# vcf_lp_4p_24db-rev1.net
KiCad netlist of a schematic drawn in EAGLE
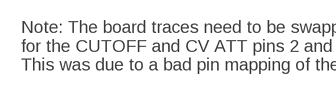
[diagram p0: schematic, sheet 1, part 1 of 2]
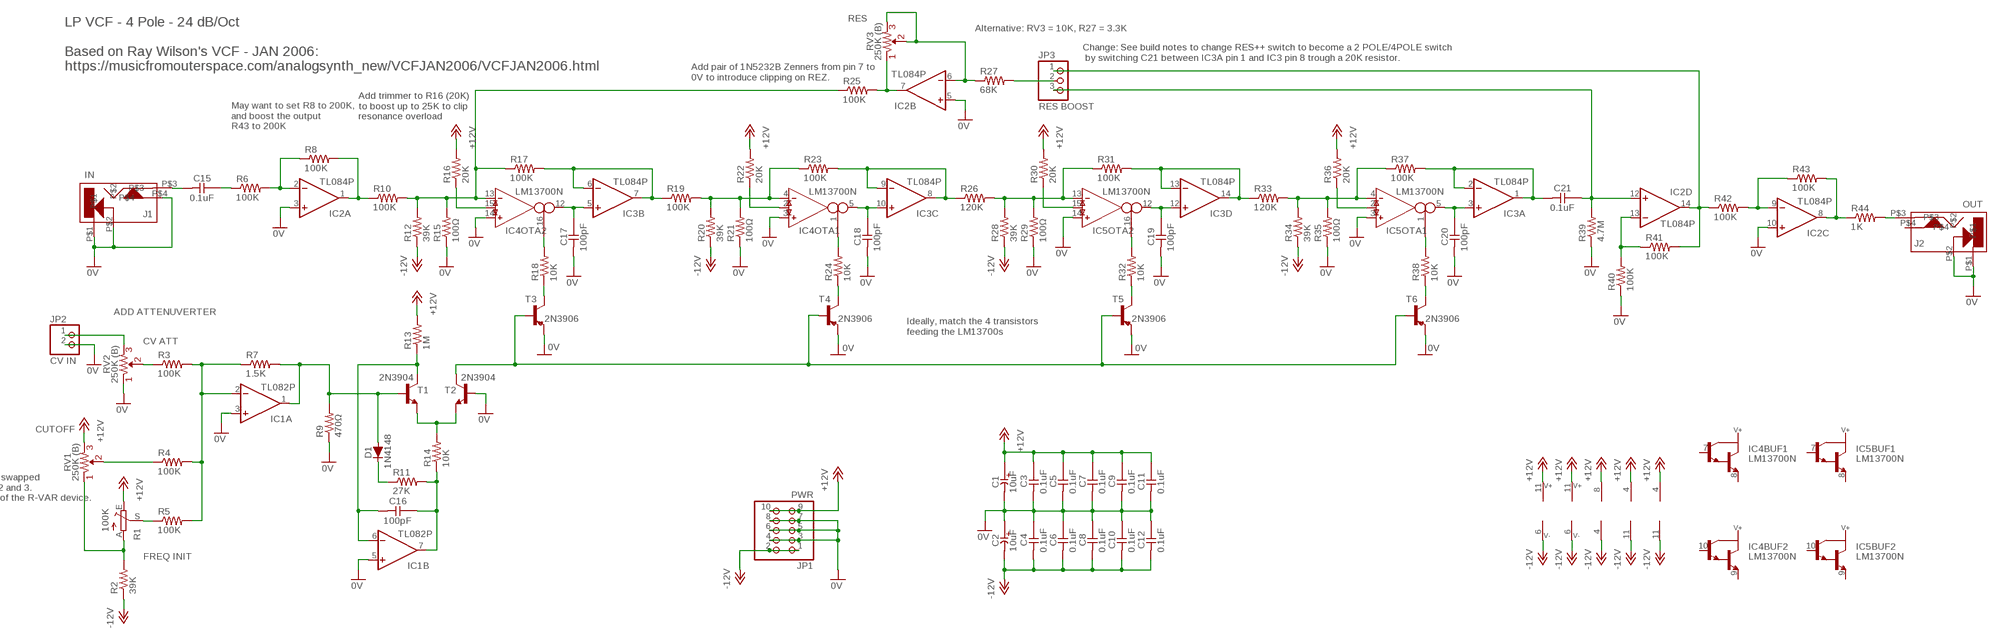
[diagram p1: schematic, sheet 1, part 2 of 2]

(export (version "E")
  (design (tool "Eeschema 10.0.6"))
  (components
    (comp (ref "C1")
      (value "10uF")
      (footprint "eagle-import:E2-5")
      (libsource (lib "eagle-import") (part "CE-USE2-5"))
    )
    (comp (ref "C2")
      (value "10uF")
      (footprint "eagle-import:E2-5")
      (libsource (lib "eagle-import") (part "CE-USE2-5"))
    )
    (comp (ref "C3")
      (value "0.1uF")
      (footprint "eagle-import:C025-024X044")
      (libsource (lib "eagle-import") (part "CC-US025-024X044"))
    )
    (comp (ref "C4")
      (value "0.1uF")
      (footprint "eagle-import:C025-024X044")
      (libsource (lib "eagle-import") (part "CC-US025-024X044"))
    )
    (comp (ref "C5")
      (value "0.1uF")
      (footprint "eagle-import:C025-024X044")
      (libsource (lib "eagle-import") (part "CC-US025-024X044"))
    )
    (comp (ref "C6")
      (value "0.1uF")
      (footprint "eagle-import:C025-024X044")
      (libsource (lib "eagle-import") (part "CC-US025-024X044"))
    )
    (comp (ref "C7")
      (value "0.1uF")
      (footprint "eagle-import:C025-024X044")
      (libsource (lib "eagle-import") (part "CC-US025-024X044"))
    )
    (comp (ref "C8")
      (value "0.1uF")
      (footprint "eagle-import:C025-024X044")
      (libsource (lib "eagle-import") (part "CC-US025-024X044"))
    )
    (comp (ref "C9")
      (value "0.1uF")
      (footprint "eagle-import:C025-024X044")
      (libsource (lib "eagle-import") (part "CC-US025-024X044"))
    )
    (comp (ref "C10")
      (value "0.1uF")
      (footprint "eagle-import:C025-024X044")
      (libsource (lib "eagle-import") (part "CC-US025-024X044"))
    )
    (comp (ref "C11")
      (value "0.1uF")
      (footprint "eagle-import:C025-024X044")
      (libsource (lib "eagle-import") (part "CC-US025-024X044"))
    )
    (comp (ref "C12")
      (value "0.1uF")
      (footprint "eagle-import:C025-024X044")
      (libsource (lib "eagle-import") (part "CC-US025-024X044"))
    )
    (comp (ref "C15")
      (value "0.1uF")
      (footprint "eagle-import:C025-024X044")
      (libsource (lib "eagle-import") (part "CC-US025-024X044"))
    )
    (comp (ref "C16")
      (value "100pF")
      (footprint "eagle-import:C025-024X044")
      (libsource (lib "eagle-import") (part "CC-US025-024X044"))
    )
    (comp (ref "C17")
      (value "100pF")
      (footprint "eagle-import:C025-024X044")
      (libsource (lib "eagle-import") (part "CC-US025-024X044"))
    )
    (comp (ref "C18")
      (value "100pF")
      (footprint "eagle-import:C025-024X044")
      (libsource (lib "eagle-import") (part "CC-US025-024X044"))
    )
    (comp (ref "C19")
      (value "100pF")
      (footprint "eagle-import:C025-024X044")
      (libsource (lib "eagle-import") (part "CC-US025-024X044"))
    )
    (comp (ref "C20")
      (value "100pF")
      (footprint "eagle-import:C025-024X044")
      (libsource (lib "eagle-import") (part "CC-US025-024X044"))
    )
    (comp (ref "C21")
      (value "0.1uF")
      (footprint "eagle-import:C025-024X044")
      (libsource (lib "eagle-import") (part "CC-US025-024X044"))
    )
    (comp (ref "D1")
      (value "1N4148")
      (footprint "eagle-import:DO35-7")
      (libsource (lib "eagle-import") (part "1N4148"))
    )
    (comp (ref "IC1")
      (value "TL082P")
      (footprint "eagle-import:DIL08")
      (libsource (lib "eagle-import") (part "TL082P"))
    )
    (comp (ref "IC2")
      (value "TL084P")
      (footprint "eagle-import:DIL14")
      (libsource (lib "eagle-import") (part "TL084P"))
    )
    (comp (ref "IC3")
      (value "TL084P")
      (footprint "eagle-import:DIL14")
      (libsource (lib "eagle-import") (part "TL084P"))
    )
    (comp (ref "IC4")
      (value "LM13700N")
      (footprint "eagle-import:DIL16")
      (libsource (lib "eagle-import") (part "LM13700N"))
    )
    (comp (ref "IC5")
      (value "LM13700N")
      (footprint "eagle-import:DIL16")
      (libsource (lib "eagle-import") (part "LM13700N"))
    )
    (comp (ref "J1")
      (value "IN")
      (footprint "eagle-import:CL1384")
      (libsource (lib "eagle-import") (part "CL1384"))
    )
    (comp (ref "J2")
      (value "OUT")
      (footprint "eagle-import:CL1384")
      (libsource (lib "eagle-import") (part "CL1384"))
    )
    (comp (ref "JP1")
      (value "PWR")
      (footprint "eagle-import:2X05")
      (libsource (lib "eagle-import") (part "PINHD-2X5"))
    )
    (comp (ref "JP2")
      (value "CV IN")
      (footprint "eagle-import:1X02")
      (libsource (lib "eagle-import") (part "PINHD-1X2"))
    )
    (comp (ref "JP3")
      (value "RES BOOST")
      (footprint "eagle-import:1X03")
      (libsource (lib "eagle-import") (part "PINHD-1X3"))
    )
    (comp (ref "R1")
      (value "100K")
      (footprint "eagle-import:CA6V")
      (libsource (lib "eagle-import") (part "TRIM_EU-CA6V"))
    )
    (comp (ref "R2")
      (value "39K")
      (footprint "eagle-import:0207_7")
      (libsource (lib "eagle-import") (part "R-US_0207/7"))
    )
    (comp (ref "R3")
      (value "100K")
      (footprint "eagle-import:0207_7")
      (libsource (lib "eagle-import") (part "R-US_0207/7"))
    )
    (comp (ref "R4")
      (value "100K")
      (footprint "eagle-import:0207_7")
      (libsource (lib "eagle-import") (part "R-US_0207/7"))
    )
    (comp (ref "R5")
      (value "100K")
      (footprint "eagle-import:0207_7")
      (libsource (lib "eagle-import") (part "R-US_0207/7"))
    )
    (comp (ref "R6")
      (value "100K")
      (footprint "eagle-import:0207_7")
      (libsource (lib "eagle-import") (part "R-US_0207/7"))
    )
    (comp (ref "R7")
      (value "1.5K")
      (footprint "eagle-import:0207_7")
      (libsource (lib "eagle-import") (part "R-US_0207/7"))
    )
    (comp (ref "R8")
      (value "100K")
      (footprint "eagle-import:0207_7")
      (libsource (lib "eagle-import") (part "R-US_0207/7"))
    )
    (comp (ref "R9")
      (value "470Ω")
      (footprint "eagle-import:0207_7")
      (libsource (lib "eagle-import") (part "R-US_0207/7"))
    )
    (comp (ref "R10")
      (value "100K")
      (footprint "eagle-import:0207_7")
      (libsource (lib "eagle-import") (part "R-US_0207/7"))
    )
    (comp (ref "R11")
      (value "27K")
      (footprint "eagle-import:0207_7")
      (libsource (lib "eagle-import") (part "R-US_0207/7"))
    )
    (comp (ref "R12")
      (value "39K")
      (footprint "eagle-import:0207_7")
      (libsource (lib "eagle-import") (part "R-US_0207/7"))
    )
    (comp (ref "R13")
      (value "1M")
      (footprint "eagle-import:0207_7")
      (libsource (lib "eagle-import") (part "R-US_0207/7"))
    )
    (comp (ref "R14")
      (value "10K")
      (footprint "eagle-import:0207_7")
      (libsource (lib "eagle-import") (part "R-US_0207/7"))
    )
    (comp (ref "R15")
      (value "100Ω")
      (footprint "eagle-import:0207_7")
      (libsource (lib "eagle-import") (part "R-US_0207/7"))
    )
    (comp (ref "R16")
      (value "20K")
      (footprint "eagle-import:0207_7")
      (libsource (lib "eagle-import") (part "R-US_0207/7"))
    )
    (comp (ref "R17")
      (value "100K")
      (footprint "eagle-import:0207_7")
      (libsource (lib "eagle-import") (part "R-US_0207/7"))
    )
    (comp (ref "R18")
      (value "10K")
      (footprint "eagle-import:0207_7")
      (libsource (lib "eagle-import") (part "R-US_0207/7"))
    )
    (comp (ref "R19")
      (value "100K")
      (footprint "eagle-import:0207_7")
      (libsource (lib "eagle-import") (part "R-US_0207/7"))
    )
    (comp (ref "R20")
      (value "39K")
      (footprint "eagle-import:0207_7")
      (libsource (lib "eagle-import") (part "R-US_0207/7"))
    )
    (comp (ref "R21")
      (value "100Ω")
      (footprint "eagle-import:0207_7")
      (libsource (lib "eagle-import") (part "R-US_0207/7"))
    )
    (comp (ref "R22")
      (value "20K")
      (footprint "eagle-import:0207_7")
      (libsource (lib "eagle-import") (part "R-US_0207/7"))
    )
    (comp (ref "R23")
      (value "100K")
      (footprint "eagle-import:0207_7")
      (libsource (lib "eagle-import") (part "R-US_0207/7"))
    )
    (comp (ref "R24")
      (value "10K")
      (footprint "eagle-import:0207_7")
      (libsource (lib "eagle-import") (part "R-US_0207/7"))
    )
    (comp (ref "R25")
      (value "100K")
      (footprint "eagle-import:0207_7")
      (libsource (lib "eagle-import") (part "R-US_0207/7"))
    )
    (comp (ref "R26")
      (value "120K")
      (footprint "eagle-import:0207_7")
      (libsource (lib "eagle-import") (part "R-US_0207/7"))
    )
    (comp (ref "R27")
      (value "68K")
      (footprint "eagle-import:0207_7")
      (libsource (lib "eagle-import") (part "R-US_0207/7"))
    )
    (comp (ref "R28")
      (value "39K")
      (footprint "eagle-import:0207_7")
      (libsource (lib "eagle-import") (part "R-US_0207/7"))
    )
    (comp (ref "R29")
      (value "100Ω")
      (footprint "eagle-import:0207_7")
      (libsource (lib "eagle-import") (part "R-US_0207/7"))
    )
    (comp (ref "R30")
      (value "20K")
      (footprint "eagle-import:0207_7")
      (libsource (lib "eagle-import") (part "R-US_0207/7"))
    )
    (comp (ref "R31")
      (value "100K")
      (footprint "eagle-import:0207_7")
      (libsource (lib "eagle-import") (part "R-US_0207/7"))
    )
    (comp (ref "R32")
      (value "10K")
      (footprint "eagle-import:0207_7")
      (libsource (lib "eagle-import") (part "R-US_0207/7"))
    )
    (comp (ref "R33")
      (value "120K")
      (footprint "eagle-import:0207_7")
      (libsource (lib "eagle-import") (part "R-US_0207/7"))
    )
    (comp (ref "R34")
      (value "39K")
      (footprint "eagle-import:0207_7")
      (libsource (lib "eagle-import") (part "R-US_0207/7"))
    )
    (comp (ref "R35")
      (value "100Ω")
      (footprint "eagle-import:0207_7")
      (libsource (lib "eagle-import") (part "R-US_0207/7"))
    )
    (comp (ref "R36")
      (value "20K")
      (footprint "eagle-import:0207_7")
      (libsource (lib "eagle-import") (part "R-US_0207/7"))
    )
    (comp (ref "R37")
      (value "100K")
      (footprint "eagle-import:0207_7")
      (libsource (lib "eagle-import") (part "R-US_0207/7"))
    )
    (comp (ref "R38")
      (value "10K")
      (footprint "eagle-import:0207_7")
      (libsource (lib "eagle-import") (part "R-US_0207/7"))
    )
    (comp (ref "R39")
      (value "4.7M")
      (footprint "eagle-import:0207_7")
      (libsource (lib "eagle-import") (part "R-US_0207/7"))
    )
    (comp (ref "R40")
      (value "100K")
      (footprint "eagle-import:0207_7")
      (libsource (lib "eagle-import") (part "R-US_0207/7"))
    )
    (comp (ref "R41")
      (value "100K")
      (footprint "eagle-import:0207_7")
      (libsource (lib "eagle-import") (part "R-US_0207/7"))
    )
    (comp (ref "R42")
      (value "100K")
      (footprint "eagle-import:0207_7")
      (libsource (lib "eagle-import") (part "R-US_0207/7"))
    )
    (comp (ref "R43")
      (value "100K")
      (footprint "eagle-import:0207_7")
      (libsource (lib "eagle-import") (part "R-US_0207/7"))
    )
    (comp (ref "R44")
      (value "1K")
      (footprint "eagle-import:0207_7")
      (libsource (lib "eagle-import") (part "R-US_0207/7"))
    )
    (comp (ref "RV1")
      (value "250K (B)")
      (footprint "eagle-import:_COMMON_3RP_1610N")
      (libsource (lib "eagle-import") (part "R-VARR-VAR-10"))
    )
    (comp (ref "RV2")
      (value "250K (B)")
      (footprint "eagle-import:_COMMON_3RP_1610N")
      (libsource (lib "eagle-import") (part "R-VARR-VAR-10"))
    )
    (comp (ref "RV3")
      (value "250K (B)")
      (footprint "eagle-import:_COMMON_3RP_1610N")
      (libsource (lib "eagle-import") (part "R-VARR-VAR-10"))
    )
    (comp (ref "T1")
      (value "2N3904")
      (footprint "eagle-import:TO92-EBC")
      (libsource (lib "eagle-import") (part "-NPN-TO92-EBC2N3904"))
    )
    (comp (ref "T2")
      (value "2N3904")
      (footprint "eagle-import:TO92-EBC")
      (libsource (lib "eagle-import") (part "-NPN-TO92-EBC2N3904"))
    )
    (comp (ref "T3")
      (value "2N3906")
      (footprint "eagle-import:TO92-EBC")
      (libsource (lib "eagle-import") (part "-PNP-TO92-EBC2N3906"))
    )
    (comp (ref "T4")
      (value "2N3906")
      (footprint "eagle-import:TO92-EBC")
      (libsource (lib "eagle-import") (part "-PNP-TO92-EBC2N3906"))
    )
    (comp (ref "T5")
      (value "2N3906")
      (footprint "eagle-import:TO92-EBC")
      (libsource (lib "eagle-import") (part "-PNP-TO92-EBC2N3906"))
    )
    (comp (ref "T6")
      (value "2N3906")
      (footprint "eagle-import:TO92-EBC")
      (libsource (lib "eagle-import") (part "-PNP-TO92-EBC2N3906"))
    )
  )
  (nets
    (net (code "1") (name "+12V") (class "Default")
      (node (ref "C1") (pin "+") (pinfunction "+_+") (pintype "passive"))
      (node (ref "C11") (pin "1") (pinfunction "1_1") (pintype "passive"))
      (node (ref "C3") (pin "1") (pinfunction "1_1") (pintype "passive"))
      (node (ref "C5") (pin "1") (pinfunction "1_1") (pintype "passive"))
      (node (ref "C7") (pin "1") (pinfunction "1_1") (pintype "passive"))
      (node (ref "C9") (pin "1") (pinfunction "1_1") (pintype "passive"))
      (node (ref "IC1") (pin "8") (pinfunction "V+_8") (pintype "power_in"))
      (node (ref "IC2") (pin "4") (pinfunction "V+_4") (pintype "power_in"))
      (node (ref "IC3") (pin "4") (pinfunction "V+_4") (pintype "power_in"))
      (node (ref "IC4") (pin "11") (pinfunction "V+_11") (pintype "power_in"))
      (node (ref "IC5") (pin "11") (pinfunction "V+_11") (pintype "power_in"))
      (node (ref "JP1") (pin "10") (pinfunction "10_10") (pintype "passive"))
      (node (ref "JP1") (pin "9") (pinfunction "9_9") (pintype "passive"))
      (node (ref "R1") (pin "E") (pinfunction "E_E") (pintype "passive"))
      (node (ref "R13") (pin "2") (pinfunction "2_2") (pintype "passive"))
      (node (ref "R16") (pin "2") (pinfunction "2_2") (pintype "passive"))
      (node (ref "R22") (pin "2") (pinfunction "2_2") (pintype "passive"))
      (node (ref "R30") (pin "2") (pinfunction "2_2") (pintype "passive"))
      (node (ref "R36") (pin "2") (pinfunction "2_2") (pintype "passive"))
      (node (ref "RV1") (pin "2") (pinfunction "2_2") (pintype "passive"))
    )
    (net (code "2") (name "-12V") (class "Default")
      (node (ref "C10") (pin "2") (pinfunction "2_2") (pintype "passive"))
      (node (ref "C12") (pin "2") (pinfunction "2_2") (pintype "passive"))
      (node (ref "C2") (pin "-") (pinfunction "-_-") (pintype "passive"))
      (node (ref "C4") (pin "2") (pinfunction "2_2") (pintype "passive"))
      (node (ref "C6") (pin "2") (pinfunction "2_2") (pintype "passive"))
      (node (ref "C8") (pin "2") (pinfunction "2_2") (pintype "passive"))
      (node (ref "IC1") (pin "4") (pinfunction "V-_4") (pintype "power_in"))
      (node (ref "IC2") (pin "11") (pinfunction "V-_11") (pintype "power_in"))
      (node (ref "IC3") (pin "11") (pinfunction "V-_11") (pintype "power_in"))
      (node (ref "IC4") (pin "6") (pinfunction "V-_6") (pintype "power_in"))
      (node (ref "IC5") (pin "6") (pinfunction "V-_6") (pintype "power_in"))
      (node (ref "JP1") (pin "1") (pinfunction "1_1") (pintype "passive"))
      (node (ref "JP1") (pin "2") (pinfunction "2_2") (pintype "passive"))
      (node (ref "R12") (pin "1") (pinfunction "1_1") (pintype "passive"))
      (node (ref "R2") (pin "1") (pinfunction "1_1") (pintype "passive"))
      (node (ref "R20") (pin "1") (pinfunction "1_1") (pintype "passive"))
      (node (ref "R28") (pin "1") (pinfunction "1_1") (pintype "passive"))
      (node (ref "R34") (pin "1") (pinfunction "1_1") (pintype "passive"))
    )
    (net (code "3") (name "0V") (class "Default")
      (node (ref "C1") (pin "-") (pinfunction "-_-") (pintype "passive"))
      (node (ref "C10") (pin "1") (pinfunction "1_1") (pintype "passive"))
      (node (ref "C11") (pin "2") (pinfunction "2_2") (pintype "passive"))
      (node (ref "C12") (pin "1") (pinfunction "1_1") (pintype "passive"))
      (node (ref "C17") (pin "2") (pinfunction "2_2") (pintype "passive"))
      (node (ref "C18") (pin "2") (pinfunction "2_2") (pintype "passive"))
      (node (ref "C19") (pin "2") (pinfunction "2_2") (pintype "passive"))
      (node (ref "C2") (pin "+") (pinfunction "+_+") (pintype "passive"))
      (node (ref "C20") (pin "2") (pinfunction "2_2") (pintype "passive"))
      (node (ref "C3") (pin "2") (pinfunction "2_2") (pintype "passive"))
      (node (ref "C4") (pin "1") (pinfunction "1_1") (pintype "passive"))
      (node (ref "C5") (pin "2") (pinfunction "2_2") (pintype "passive"))
      (node (ref "C6") (pin "1") (pinfunction "1_1") (pintype "passive"))
      (node (ref "C7") (pin "2") (pinfunction "2_2") (pintype "passive"))
      (node (ref "C8") (pin "1") (pinfunction "1_1") (pintype "passive"))
      (node (ref "C9") (pin "2") (pinfunction "2_2") (pintype "passive"))
      (node (ref "IC1") (pin "3") (pinfunction "+IN_3") (pintype "input"))
      (node (ref "IC1") (pin "5") (pinfunction "+IN_5") (pintype "input"))
      (node (ref "IC2") (pin "10") (pinfunction "+IN_10") (pintype "input"))
      (node (ref "IC2") (pin "3") (pinfunction "+IN_3") (pintype "input"))
      (node (ref "IC2") (pin "5") (pinfunction "+IN_5") (pintype "input"))
      (node (ref "IC4") (pin "14") (pinfunction "IN_P_14") (pintype "input"))
      (node (ref "IC4") (pin "3") (pinfunction "IN_P_3") (pintype "input"))
      (node (ref "IC5") (pin "14") (pinfunction "IN_P_14") (pintype "input"))
      (node (ref "IC5") (pin "3") (pinfunction "IN_P_3") (pintype "input"))
      (node (ref "J1") (pin "P$1") (pinfunction "P$1_P$1") (pintype "bidirectional"))
      (node (ref "J1") (pin "P$2") (pinfunction "P$2_P$2") (pintype "bidirectional"))
      (node (ref "J1") (pin "P$4") (pinfunction "P$4_P$4") (pintype "bidirectional"))
      (node (ref "J2") (pin "P$1") (pinfunction "P$1_P$1") (pintype "bidirectional"))
      (node (ref "J2") (pin "P$2") (pinfunction "P$2_P$2") (pintype "bidirectional"))
      (node (ref "JP1") (pin "3") (pinfunction "3_3") (pintype "passive"))
      (node (ref "JP1") (pin "4") (pinfunction "4_4") (pintype "passive"))
      (node (ref "JP1") (pin "5") (pinfunction "5_5") (pintype "passive"))
      (node (ref "JP1") (pin "6") (pinfunction "6_6") (pintype "passive"))
      (node (ref "JP1") (pin "7") (pinfunction "7_7") (pintype "passive"))
      (node (ref "JP1") (pin "8") (pinfunction "8_8") (pintype "passive"))
      (node (ref "JP2") (pin "2") (pinfunction "2_2") (pintype "passive"))
      (node (ref "R15") (pin "1") (pinfunction "1_1") (pintype "passive"))
      (node (ref "R21") (pin "1") (pinfunction "1_1") (pintype "passive"))
      (node (ref "R29") (pin "1") (pinfunction "1_1") (pintype "passive"))
      (node (ref "R35") (pin "1") (pinfunction "1_1") (pintype "passive"))
      (node (ref "R39") (pin "1") (pinfunction "1_1") (pintype "passive"))
      (node (ref "R40") (pin "1") (pinfunction "1_1") (pintype "passive"))
      (node (ref "R9") (pin "1") (pinfunction "1_1") (pintype "passive"))
      (node (ref "RV2") (pin "1") (pinfunction "1_1") (pintype "passive"))
      (node (ref "T2") (pin "B") (pinfunction "B_B") (pintype "passive"))
      (node (ref "T3") (pin "E") (pinfunction "E_E") (pintype "passive"))
      (node (ref "T4") (pin "E") (pinfunction "E_E") (pintype "passive"))
      (node (ref "T5") (pin "E") (pinfunction "E_E") (pintype "passive"))
      (node (ref "T6") (pin "E") (pinfunction "E_E") (pintype "passive"))
    )
    (net (code "4") (name "Net-(C15-Pad1)") (class "Default")
      (node (ref "C15") (pin "1") (pinfunction "1_1") (pintype "passive"))
      (node (ref "R6") (pin "1") (pinfunction "1_1") (pintype "passive"))
    )
    (net (code "5") (name "Net-(C15-Pad2)") (class "Default")
      (node (ref "C15") (pin "2") (pinfunction "2_2") (pintype "passive"))
      (node (ref "J1") (pin "P$3") (pinfunction "P$3_P$3") (pintype "bidirectional"))
    )
    (net (code "6") (name "Net-(D1-PadC)") (class "Default")
      (node (ref "D1") (pin "C") (pinfunction "C_C") (pintype "passive"))
      (node (ref "R11") (pin "1") (pinfunction "1_1") (pintype "passive"))
    )
    (net (code "7") (name "Net-(IC1A--IN)") (class "Default")
      (node (ref "IC1") (pin "2") (pinfunction "-IN_2") (pintype "input"))
      (node (ref "R3") (pin "2") (pinfunction "2_2") (pintype "passive"))
      (node (ref "R4") (pin "2") (pinfunction "2_2") (pintype "passive"))
      (node (ref "R5") (pin "2") (pinfunction "2_2") (pintype "passive"))
      (node (ref "R7") (pin "1") (pinfunction "1_1") (pintype "passive"))
    )
    (net (code "8") (name "Net-(IC1A-OUT)") (class "Default")
      (node (ref "D1") (pin "A") (pinfunction "A_A") (pintype "passive"))
      (node (ref "IC1") (pin "1") (pinfunction "OUT_1") (pintype "output"))
      (node (ref "R7") (pin "2") (pinfunction "2_2") (pintype "passive"))
      (node (ref "R9") (pin "2") (pinfunction "2_2") (pintype "passive"))
      (node (ref "T1") (pin "B") (pinfunction "B_B") (pintype "passive"))
    )
    (net (code "9") (name "Net-(IC1B--IN)") (class "Default")
      (node (ref "C16") (pin "2") (pinfunction "2_2") (pintype "passive"))
      (node (ref "IC1") (pin "6") (pinfunction "-IN_6") (pintype "input"))
      (node (ref "R13") (pin "1") (pinfunction "1_1") (pintype "passive"))
      (node (ref "T1") (pin "C") (pinfunction "C_C") (pintype "passive"))
    )
    (net (code "10") (name "Net-(IC1B-OUT)") (class "Default")
      (node (ref "C16") (pin "1") (pinfunction "1_1") (pintype "passive"))
      (node (ref "IC1") (pin "7") (pinfunction "OUT_7") (pintype "output"))
      (node (ref "R11") (pin "2") (pinfunction "2_2") (pintype "passive"))
      (node (ref "R14") (pin "1") (pinfunction "1_1") (pintype "passive"))
    )
    (net (code "11") (name "Net-(IC2A--IN)") (class "Default")
      (node (ref "IC2") (pin "2") (pinfunction "-IN_2") (pintype "input"))
      (node (ref "R6") (pin "2") (pinfunction "2_2") (pintype "passive"))
      (node (ref "R8") (pin "1") (pinfunction "1_1") (pintype "passive"))
    )
    (net (code "12") (name "Net-(IC2A-OUT)") (class "Default")
      (node (ref "IC2") (pin "1") (pinfunction "OUT_1") (pintype "output"))
      (node (ref "R10") (pin "1") (pinfunction "1_1") (pintype "passive"))
      (node (ref "R8") (pin "2") (pinfunction "2_2") (pintype "passive"))
    )
    (net (code "13") (name "Net-(IC2B--IN)") (class "Default")
      (node (ref "IC2") (pin "6") (pinfunction "-IN_6") (pintype "input"))
      (node (ref "R27") (pin "1") (pinfunction "1_1") (pintype "passive"))
      (node (ref "RV3") (pin "2") (pinfunction "2_2") (pintype "passive"))
      (node (ref "RV3") (pin "3") (pinfunction "P$1_3") (pintype "passive"))
    )
    (net (code "14") (name "Net-(IC2B-OUT)") (class "Default")
      (node (ref "IC2") (pin "7") (pinfunction "OUT_7") (pintype "output"))
      (node (ref "R25") (pin "2") (pinfunction "2_2") (pintype "passive"))
      (node (ref "RV3") (pin "1") (pinfunction "1_1") (pintype "passive"))
    )
    (net (code "15") (name "Net-(IC2C--IN)") (class "Default")
      (node (ref "IC2") (pin "9") (pinfunction "-IN_9") (pintype "input"))
      (node (ref "R42") (pin "2") (pinfunction "2_2") (pintype "passive"))
      (node (ref "R43") (pin "1") (pinfunction "1_1") (pintype "passive"))
    )
    (net (code "16") (name "Net-(IC2C-OUT)") (class "Default")
      (node (ref "IC2") (pin "8") (pinfunction "OUT_8") (pintype "output"))
      (node (ref "R43") (pin "2") (pinfunction "2_2") (pintype "passive"))
      (node (ref "R44") (pin "1") (pinfunction "1_1") (pintype "passive"))
    )
    (net (code "17") (name "Net-(IC2D-+IN)") (class "Default")
      (node (ref "C21") (pin "1") (pinfunction "1_1") (pintype "passive"))
      (node (ref "IC2") (pin "12") (pinfunction "+IN_12") (pintype "input"))
      (node (ref "JP3") (pin "3") (pinfunction "3_3") (pintype "passive"))
      (node (ref "R39") (pin "2") (pinfunction "2_2") (pintype "passive"))
    )
    (net (code "18") (name "Net-(IC2D--IN)") (class "Default")
      (node (ref "IC2") (pin "13") (pinfunction "-IN_13") (pintype "input"))
      (node (ref "R40") (pin "2") (pinfunction "2_2") (pintype "passive"))
      (node (ref "R41") (pin "1") (pinfunction "1_1") (pintype "passive"))
    )
    (net (code "19") (name "Net-(IC2D-OUT)") (class "Default")
      (node (ref "IC2") (pin "14") (pinfunction "OUT_14") (pintype "output"))
      (node (ref "JP3") (pin "1") (pinfunction "1_1") (pintype "passive"))
      (node (ref "R41") (pin "2") (pinfunction "2_2") (pintype "passive"))
      (node (ref "R42") (pin "1") (pinfunction "1_1") (pintype "passive"))
    )
    (net (code "20") (name "Net-(IC3A-+IN)") (class "Default")
      (node (ref "C20") (pin "1") (pinfunction "1_1") (pintype "passive"))
      (node (ref "IC3") (pin "3") (pinfunction "+IN_3") (pintype "input"))
      (node (ref "IC5") (pin "5") (pinfunction "OUT_5") (pintype "output"))
    )
    (net (code "21") (name "Net-(IC3A--IN)") (class "Default")
      (node (ref "C21") (pin "2") (pinfunction "2_2") (pintype "passive"))
      (node (ref "IC3") (pin "1") (pinfunction "OUT_1") (pintype "output"))
      (node (ref "IC3") (pin "2") (pinfunction "-IN_2") (pintype "input"))
      (node (ref "R37") (pin "2") (pinfunction "2_2") (pintype "passive"))
    )
    (net (code "22") (name "Net-(IC3B-+IN)") (class "Default")
      (node (ref "C17") (pin "1") (pinfunction "1_1") (pintype "passive"))
      (node (ref "IC3") (pin "5") (pinfunction "+IN_5") (pintype "input"))
      (node (ref "IC4") (pin "12") (pinfunction "OUT_12") (pintype "output"))
    )
    (net (code "23") (name "Net-(IC3B--IN)") (class "Default")
      (node (ref "IC3") (pin "6") (pinfunction "-IN_6") (pintype "input"))
      (node (ref "IC3") (pin "7") (pinfunction "OUT_7") (pintype "output"))
      (node (ref "R17") (pin "2") (pinfunction "2_2") (pintype "passive"))
      (node (ref "R19") (pin "1") (pinfunction "1_1") (pintype "passive"))
    )
    (net (code "24") (name "Net-(IC3C-+IN)") (class "Default")
      (node (ref "C18") (pin "1") (pinfunction "1_1") (pintype "passive"))
      (node (ref "IC3") (pin "10") (pinfunction "+IN_10") (pintype "input"))
      (node (ref "IC4") (pin "5") (pinfunction "OUT_5") (pintype "output"))
    )
    (net (code "25") (name "Net-(IC3C--IN)") (class "Default")
      (node (ref "IC3") (pin "8") (pinfunction "OUT_8") (pintype "output"))
      (node (ref "IC3") (pin "9") (pinfunction "-IN_9") (pintype "input"))
      (node (ref "R23") (pin "2") (pinfunction "2_2") (pintype "passive"))
      (node (ref "R26") (pin "1") (pinfunction "1_1") (pintype "passive"))
    )
    (net (code "26") (name "Net-(IC3D-+IN)") (class "Default")
      (node (ref "C19") (pin "1") (pinfunction "1_1") (pintype "passive"))
      (node (ref "IC3") (pin "12") (pinfunction "+IN_12") (pintype "input"))
      (node (ref "IC5") (pin "12") (pinfunction "OUT_12") (pintype "output"))
    )
    (net (code "27") (name "Net-(IC3D--IN)") (class "Default")
      (node (ref "IC3") (pin "13") (pinfunction "-IN_13") (pintype "input"))
      (node (ref "IC3") (pin "14") (pinfunction "OUT_14") (pintype "output"))
      (node (ref "R31") (pin "2") (pinfunction "2_2") (pintype "passive"))
      (node (ref "R33") (pin "1") (pinfunction "1_1") (pintype "passive"))
    )
    (net (code "28") (name "Net-(IC4C-IN_N)") (class "Default")
      (node (ref "IC4") (pin "4") (pinfunction "IN_N_4") (pintype "input"))
      (node (ref "R19") (pin "2") (pinfunction "2_2") (pintype "passive"))
      (node (ref "R20") (pin "2") (pinfunction "2_2") (pintype "passive"))
      (node (ref "R21") (pin "2") (pinfunction "2_2") (pintype "passive"))
      (node (ref "R23") (pin "1") (pinfunction "1_1") (pintype "passive"))
    )
    (net (code "29") (name "Net-(IC4C-I_BIAS)") (class "Default")
      (node (ref "IC4") (pin "1") (pinfunction "I_BIAS_1") (pintype "input"))
      (node (ref "R24") (pin "2") (pinfunction "2_2") (pintype "passive"))
    )
    (net (code "30") (name "Net-(IC4C-I_DIODE)") (class "Default")
      (node (ref "IC4") (pin "2") (pinfunction "I_DIODE_2") (pintype "input"))
      (node (ref "R22") (pin "1") (pinfunction "1_1") (pintype "passive"))
    )
    (net (code "31") (name "Net-(IC4D-IN_N)") (class "Default")
      (node (ref "IC4") (pin "13") (pinfunction "IN_N_13") (pintype "input"))
      (node (ref "R10") (pin "2") (pinfunction "2_2") (pintype "passive"))
      (node (ref "R12") (pin "2") (pinfunction "2_2") (pintype "passive"))
      (node (ref "R15") (pin "2") (pinfunction "2_2") (pintype "passive"))
      (node (ref "R17") (pin "1") (pinfunction "1_1") (pintype "passive"))
      (node (ref "R25") (pin "1") (pinfunction "1_1") (pintype "passive"))
    )
    (net (code "32") (name "Net-(IC4D-I_BIAS)") (class "Default")
      (node (ref "IC4") (pin "16") (pinfunction "I_BIAS_16") (pintype "input"))
      (node (ref "R18") (pin "2") (pinfunction "2_2") (pintype "passive"))
    )
    (net (code "33") (name "Net-(IC4D-I_DIODE)") (class "Default")
      (node (ref "IC4") (pin "15") (pinfunction "I_DIODE_15") (pintype "input"))
      (node (ref "R16") (pin "1") (pinfunction "1_1") (pintype "passive"))
    )
    (net (code "34") (name "Net-(IC5C-IN_N)") (class "Default")
      (node (ref "IC5") (pin "4") (pinfunction "IN_N_4") (pintype "input"))
      (node (ref "R33") (pin "2") (pinfunction "2_2") (pintype "passive"))
      (node (ref "R34") (pin "2") (pinfunction "2_2") (pintype "passive"))
      (node (ref "R35") (pin "2") (pinfunction "2_2") (pintype "passive"))
      (node (ref "R37") (pin "1") (pinfunction "1_1") (pintype "passive"))
    )
    (net (code "35") (name "Net-(IC5C-I_BIAS)") (class "Default")
      (node (ref "IC5") (pin "1") (pinfunction "I_BIAS_1") (pintype "input"))
      (node (ref "R38") (pin "2") (pinfunction "2_2") (pintype "passive"))
    )
    (net (code "36") (name "Net-(IC5C-I_DIODE)") (class "Default")
      (node (ref "IC5") (pin "2") (pinfunction "I_DIODE_2") (pintype "input"))
      (node (ref "R36") (pin "1") (pinfunction "1_1") (pintype "passive"))
    )
    (net (code "37") (name "Net-(IC5D-IN_N)") (class "Default")
      (node (ref "IC5") (pin "13") (pinfunction "IN_N_13") (pintype "input"))
      (node (ref "R26") (pin "2") (pinfunction "2_2") (pintype "passive"))
      (node (ref "R28") (pin "2") (pinfunction "2_2") (pintype "passive"))
      (node (ref "R29") (pin "2") (pinfunction "2_2") (pintype "passive"))
      (node (ref "R31") (pin "1") (pinfunction "1_1") (pintype "passive"))
    )
    (net (code "38") (name "Net-(IC5D-I_BIAS)") (class "Default")
      (node (ref "IC5") (pin "16") (pinfunction "I_BIAS_16") (pintype "input"))
      (node (ref "R32") (pin "2") (pinfunction "2_2") (pintype "passive"))
    )
    (net (code "39") (name "Net-(IC5D-I_DIODE)") (class "Default")
      (node (ref "IC5") (pin "15") (pinfunction "I_DIODE_15") (pintype "input"))
      (node (ref "R30") (pin "1") (pinfunction "1_1") (pintype "passive"))
    )
    (net (code "40") (name "Net-(J2-PadP$3)") (class "Default")
      (node (ref "J2") (pin "P$3") (pinfunction "P$3_P$3") (pintype "bidirectional"))
      (node (ref "R44") (pin "2") (pinfunction "2_2") (pintype "passive"))
    )
    (net (code "41") (name "Net-(JP2-Pad1)") (class "Default")
      (node (ref "JP2") (pin "1") (pinfunction "1_1") (pintype "passive"))
      (node (ref "RV2") (pin "2") (pinfunction "2_2") (pintype "passive"))
    )
    (net (code "42") (name "Net-(JP3-Pad2)") (class "Default")
      (node (ref "JP3") (pin "2") (pinfunction "2_2") (pintype "passive"))
      (node (ref "R27") (pin "2") (pinfunction "2_2") (pintype "passive"))
    )
    (net (code "43") (name "Net-(R1-PadA)") (class "Default")
      (node (ref "R1") (pin "A") (pinfunction "A_A") (pintype "passive"))
      (node (ref "R2") (pin "2") (pinfunction "2_2") (pintype "passive"))
      (node (ref "RV1") (pin "1") (pinfunction "1_1") (pintype "passive"))
    )
    (net (code "44") (name "Net-(R1-PadS)") (class "Default")
      (node (ref "R1") (pin "S") (pinfunction "S_S") (pintype "passive"))
      (node (ref "R5") (pin "1") (pinfunction "1_1") (pintype "passive"))
    )
    (net (code "45") (name "Net-(R14-Pad2)") (class "Default")
      (node (ref "R14") (pin "2") (pinfunction "2_2") (pintype "passive"))
      (node (ref "T1") (pin "E") (pinfunction "E_E") (pintype "passive"))
      (node (ref "T2") (pin "E") (pinfunction "E_E") (pintype "passive"))
    )
    (net (code "46") (name "Net-(R18-Pad1)") (class "Default")
      (node (ref "R18") (pin "1") (pinfunction "1_1") (pintype "passive"))
      (node (ref "T3") (pin "C") (pinfunction "C_C") (pintype "passive"))
    )
    (net (code "47") (name "Net-(R24-Pad1)") (class "Default")
      (node (ref "R24") (pin "1") (pinfunction "1_1") (pintype "passive"))
      (node (ref "T4") (pin "C") (pinfunction "C_C") (pintype "passive"))
    )
    (net (code "48") (name "Net-(R32-Pad1)") (class "Default")
      (node (ref "R32") (pin "1") (pinfunction "1_1") (pintype "passive"))
      (node (ref "T5") (pin "C") (pinfunction "C_C") (pintype "passive"))
    )
    (net (code "49") (name "Net-(R38-Pad1)") (class "Default")
      (node (ref "R38") (pin "1") (pinfunction "1_1") (pintype "passive"))
      (node (ref "T6") (pin "C") (pinfunction "C_C") (pintype "passive"))
    )
    (net (code "50") (name "Net-(RV1-P$1)") (class "Default")
      (node (ref "R4") (pin "1") (pinfunction "1_1") (pintype "passive"))
      (node (ref "RV1") (pin "3") (pinfunction "P$1_3") (pintype "passive"))
    )
    (net (code "51") (name "Net-(RV2-P$1)") (class "Default")
      (node (ref "R3") (pin "1") (pinfunction "1_1") (pintype "passive"))
      (node (ref "RV2") (pin "3") (pinfunction "P$1_3") (pintype "passive"))
    )
    (net (code "52") (name "Net-(T2-PadC)") (class "Default")
      (node (ref "T2") (pin "C") (pinfunction "C_C") (pintype "passive"))
      (node (ref "T3") (pin "B") (pinfunction "B_B") (pintype "passive"))
      (node (ref "T4") (pin "B") (pinfunction "B_B") (pintype "passive"))
      (node (ref "T5") (pin "B") (pinfunction "B_B") (pintype "passive"))
      (node (ref "T6") (pin "B") (pinfunction "B_B") (pintype "passive"))
    )
    (net (code "53") (name "unconnected-(IC4A-B-Pad7)") (class "Default")
      (node (ref "IC4") (pin "7") (pinfunction "B_7") (pintype "passive"))
    )
    (net (code "54") (name "unconnected-(IC4A-E-Pad8)") (class "Default")
      (node (ref "IC4") (pin "8") (pinfunction "E_8") (pintype "passive"))
    )
    (net (code "55") (name "unconnected-(IC4B-B-Pad10)") (class "Default")
      (node (ref "IC4") (pin "10") (pinfunction "B_10") (pintype "passive"))
    )
    (net (code "56") (name "unconnected-(IC4B-E-Pad9)") (class "Default")
      (node (ref "IC4") (pin "9") (pinfunction "E_9") (pintype "passive"))
    )
    (net (code "57") (name "unconnected-(IC5A-B-Pad7)") (class "Default")
      (node (ref "IC5") (pin "7") (pinfunction "B_7") (pintype "passive"))
    )
    (net (code "58") (name "unconnected-(IC5A-E-Pad8)") (class "Default")
      (node (ref "IC5") (pin "8") (pinfunction "E_8") (pintype "passive"))
    )
    (net (code "59") (name "unconnected-(IC5B-B-Pad10)") (class "Default")
      (node (ref "IC5") (pin "10") (pinfunction "B_10") (pintype "passive"))
    )
    (net (code "60") (name "unconnected-(IC5B-E-Pad9)") (class "Default")
      (node (ref "IC5") (pin "9") (pinfunction "E_9") (pintype "passive"))
    )
    (net (code "61") (name "unconnected-(J2-PadP$4)") (class "Default")
      (node (ref "J2") (pin "P$4") (pinfunction "P$4_P$4") (pintype "bidirectional"))
    )
  )
)
